# Temp_Measurements.net
KiCad netlist of a schematic drawn in Altium Designer
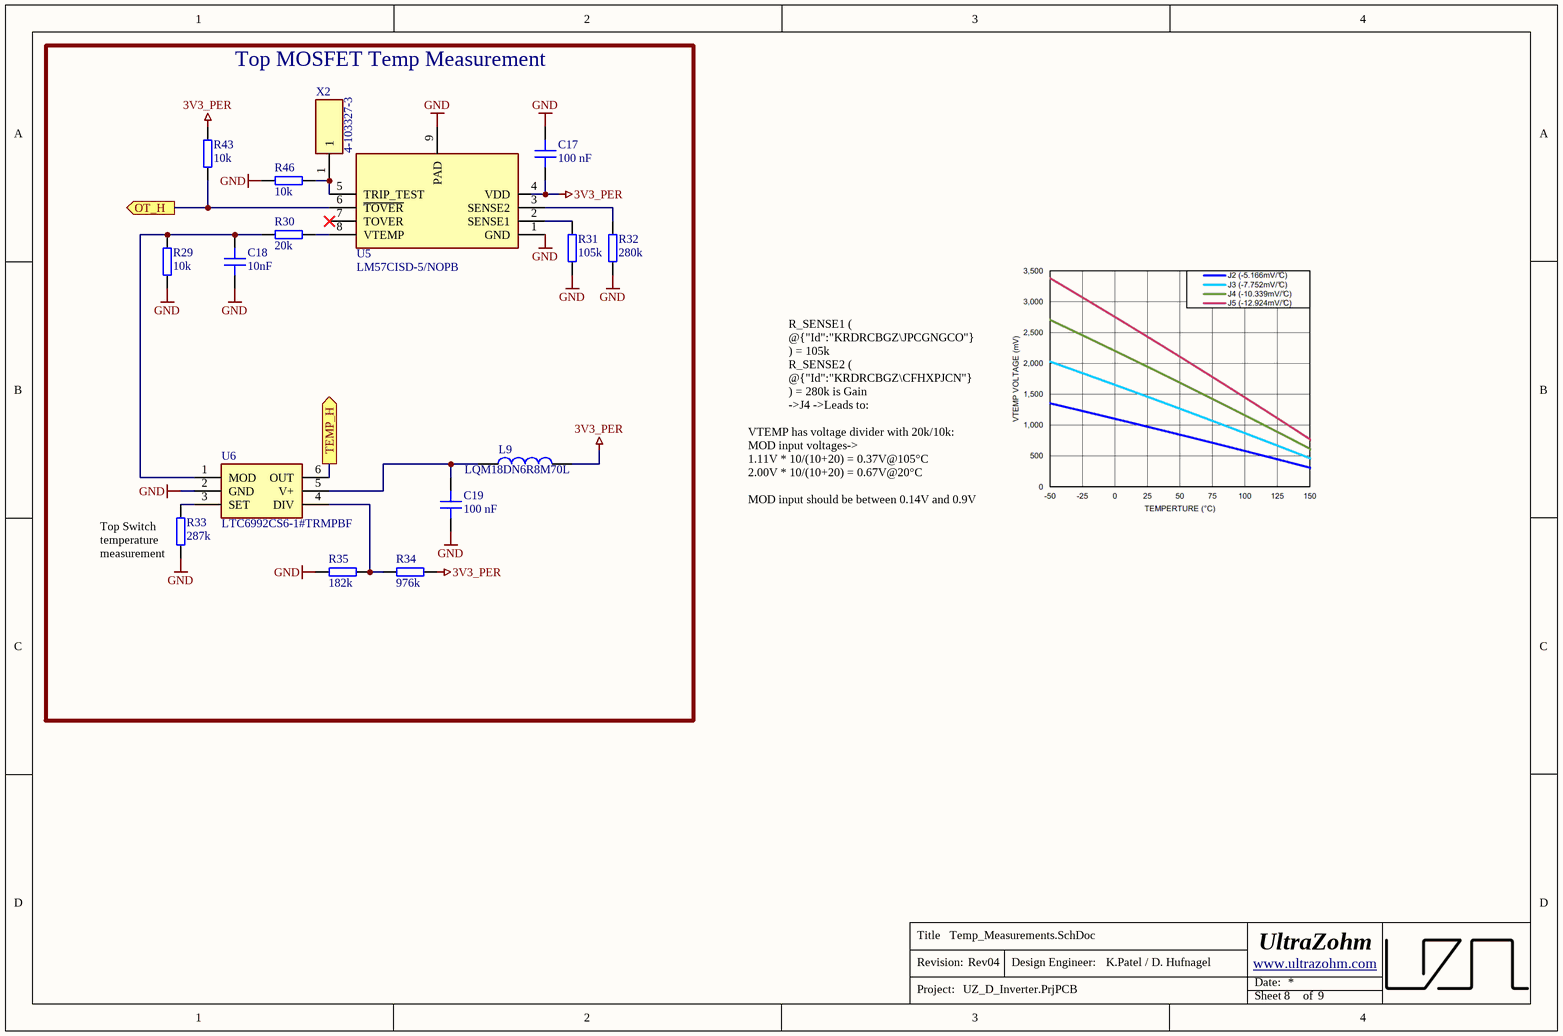
[diagram p0: Temp_Measurements.SchDoc]

(export (version "E")
  (design (tool "Eeschema 10.0.6"))
  (components
    (comp (ref "C17")
      (value "100 nF")
      (footprint "C_0603")
      (description "100V 100nF X7S ±10% 0603 Multilayer Ceramic Capacitors MLCC - SMD/SMT ROHS")
      (fields
        (field (name "MANUFACTURER PART NUMBER") "C1608X7S2A104KT000N")
        (field (name "MANUFACTURER") "TDK")
        (field (name "CREATED FROM") "AGeiger")
      )
      (libsource (lib "user") (part "Capacitor"))
    )
    (comp (ref "C18")
      (value "10nF")
      (footprint "C_0603")
      (description "50V 10nF 2X1 ±10%")
      (fields
        (field (name "MANUFACTURER PART NUMBER") "CT41G-0603-2X1-50V-0.01μF-K(N)")
        (field (name "MANUFACTURER") "TORCH")
        (field (name "CREATED FROM") "KIlhan")
      )
      (libsource (lib "user") (part "Capacitor"))
    )
    (comp (ref "C19")
      (value "100 nF")
      (footprint "C_0603")
      (description "100V 100nF X7S ±10% 0603 Multilayer Ceramic Capacitors MLCC - SMD/SMT ROHS")
      (fields
        (field (name "MANUFACTURER PART NUMBER") "C1608X7S2A104KT000N")
        (field (name "MANUFACTURER") "TDK")
        (field (name "CREATED FROM") "AGeiger")
      )
      (libsource (lib "user") (part "Capacitor"))
    )
    (comp (ref "L9")
      (value "LQM18DN6R8M70L")
      (footprint "INDC1608X95N")
      (description "6.8µH, 120mA, 0603, 740mOhm, 20%")
      (fields
        (field (name "MF") "EPCOS / TDK")
        (field (name "MPN") "B82464G4154M")
        (field (name "CREATED FROM") "DHufnagel")
      )
      (libsource (lib "user") (part "B82464G4154M"))
    )
    (comp (ref "R29")
      (value "10k")
      (footprint "RES 0603_1608")
      (description "SMD resistor E24 series")
      (fields
        (field (name "MANUFACTURER PART NUMBER") "RK73B1JTTD103J")
        (field (name "MANUFACTURER") "KOA Speer")
        (field (name "CREATED FROM") "MGremer")
      )
      (libsource (lib "user") (part "Resistor"))
    )
    (comp (ref "R30")
      (value "20k")
      (footprint "RES 0603_1608")
      (description "SMD resistor E24 series")
      (fields
        (field (name "MANUFACTURER PART NUMBER") "RK73B1JTTD203J")
        (field (name "MANUFACTURER") "KOA Speer")
        (field (name "CREATED FROM") "MGremer")
      )
      (libsource (lib "user") (part "Resistor"))
    )
    (comp (ref "R31")
      (value "105k")
      (footprint "RES 0603_1608")
      (description "SMD resistor 1%, 50V, 100ppm")
      (fields
        (field (name "MANUFACTURER PART NUMBER") "CR0603-FX-1053ELF")
        (field (name "MANUFACTURER") "Bourns")
        (field (name "CREATED FROM") "DHufnagel")
      )
      (libsource (lib "user") (part "Resistor"))
    )
    (comp (ref "R32")
      (value "280k")
      (footprint "RES 0603_1608")
      (description "SMD resistor 1%, 50V, 100ppm")
      (fields
        (field (name "MANUFACTURER PART NUMBER") "CR0603-FX-2803ELF")
        (field (name "MANUFACTURER") "Bourns")
        (field (name "CREATED FROM") "DHufnagel")
      )
      (libsource (lib "user") (part "Resistor"))
    )
    (comp (ref "R33")
      (value "287k")
      (footprint "RES 0805_2012")
      (description "SMD resistor 1%")
      (fields
        (field (name "MANUFACTURER PART NUMBER") "ERJ-6ENF2873V")
        (field (name "MANUFACTURER") "Panasonic")
        (field (name "CREATED FROM") "MGremer")
      )
      (libsource (lib "user") (part "Resistor"))
    )
    (comp (ref "R34")
      (value "976k")
      (footprint "RES 0603_1608")
      (description "SMD resistor 1%, 50V, 100ppm")
      (fields
        (field (name "MANUFACTURER PART NUMBER") "CR0603-FX-9763ELF")
        (field (name "MANUFACTURER") "Bourns")
        (field (name "CREATED FROM") "DHufnagel")
      )
      (libsource (lib "user") (part "Resistor"))
    )
    (comp (ref "R35")
      (value "182k")
      (footprint "RES 0603_1608")
      (description "SMD resistor 1%, 50V, 100ppm")
      (fields
        (field (name "MANUFACTURER PART NUMBER") "CR0603-FX-1823ELF")
        (field (name "MANUFACTURER") "Bourns")
        (field (name "CREATED FROM") "DHufnagel")
      )
      (libsource (lib "user") (part "Resistor"))
    )
    (comp (ref "R43")
      (value "10k")
      (footprint "RES 0603_1608")
      (description "SMD resistor E24 series")
      (fields
        (field (name "MANUFACTURER PART NUMBER") "RK73B1JTTD103J")
        (field (name "MANUFACTURER") "KOA Speer")
        (field (name "CREATED FROM") "MGremer")
      )
      (libsource (lib "user") (part "Resistor"))
    )
    (comp (ref "R46")
      (value "10k")
      (footprint "RES 0603_1608")
      (description "SMD resistor E24 series")
      (fields
        (field (name "MANUFACTURER PART NUMBER") "RK73B1JTTD103J")
        (field (name "MANUFACTURER") "KOA Speer")
        (field (name "CREATED FROM") "MGremer")
      )
      (libsource (lib "user") (part "Resistor"))
    )
    (comp (ref "U5")
      (value "LM57CISD-5/NOPB")
      (footprint "SON50P250X250X80-9N")
      (description "Board Mount Temperature Sensor, -50 - 150°C")
      (fields
        (field (name "MANUFACTURER") "Texas Instruments")
        (field (name "LCSC PART NUMBER") "C2864092")
        (field (name "CREATED FROM") "DHufnagel")
      )
      (libsource (lib "user") (part "LM57CISD-10_NOPB"))
    )
    (comp (ref "U6")
      (value "LTC6992CS6-1#TRMPBF")
      (footprint "SOT95P280X100-6N")
      (description "Switching Controllers PWM with 0% to 100% Pulse Width Control")
      (fields
        (field (name "MANUFACTURER") "Analog Devices")
        (field (name "LCSC PART NUMBER") "C581034")
        (field (name "CREATED FROM") "AGeiger")
      )
      (libsource (lib "user") (part "LTC6992HS6-4#WTRMPBF"))
    )
    (comp (ref "X2")
      (value "4-103327-3")
      (footprint "1_Pin_Header")
      (description "Pin Header, 2.54mm, 1 Pin")
      (fields (field (name "MANUFACTURER") "TE Connectivity") (field (name "CREATED FROM") "DHufnagel"))
      (libsource (lib "user") (part "4-103327-3"))
    )
  )
  (nets
    (net (code "1") (name "/OT_H") (class "Default")
      (node (ref "R43") (pin "2") (pinfunction "2_2") (pintype "passive"))
      (node (ref "U5") (pin "6") (pinfunction "~{TOVER}_6") (pintype "passive"))
    )
    (net (code "2") (name "/TEMP_H") (class "Default")
      (node (ref "U6") (pin "6") (pinfunction "OUT_6") (pintype "passive"))
    )
    (net (code "3") (name "3V3_PER") (class "Default")
      (node (ref "C17") (pin "1") (pinfunction "1_1") (pintype "passive"))
      (node (ref "L9") (pin "2") (pinfunction "2_2") (pintype "passive"))
      (node (ref "R34") (pin "2") (pinfunction "2_2") (pintype "passive"))
      (node (ref "R43") (pin "1") (pinfunction "1_1") (pintype "passive"))
      (node (ref "U5") (pin "4") (pinfunction "VDD_4") (pintype "passive"))
    )
    (net (code "4") (name "GND") (class "Default")
      (node (ref "C17") (pin "2") (pinfunction "2_2") (pintype "passive"))
      (node (ref "C18") (pin "1") (pinfunction "1_1") (pintype "passive"))
      (node (ref "C19") (pin "1") (pinfunction "1_1") (pintype "passive"))
      (node (ref "R29") (pin "2") (pinfunction "2_2") (pintype "passive"))
      (node (ref "R31") (pin "1") (pinfunction "1_1") (pintype "passive"))
      (node (ref "R32") (pin "1") (pinfunction "1_1") (pintype "passive"))
      (node (ref "R33") (pin "1") (pinfunction "1_1") (pintype "passive"))
      (node (ref "R35") (pin "1") (pinfunction "1_1") (pintype "passive"))
      (node (ref "R46") (pin "2") (pinfunction "2_2") (pintype "passive"))
      (node (ref "U5") (pin "1") (pinfunction "GND_1") (pintype "passive"))
      (node (ref "U5") (pin "9") (pinfunction "PAD_9") (pintype "passive"))
      (node (ref "U6") (pin "2") (pinfunction "GND_2") (pintype "passive"))
    )
    (net (code "5") (name "Net-(U5-SENSE1)") (class "Default")
      (node (ref "R31") (pin "2") (pinfunction "2_2") (pintype "passive"))
      (node (ref "U5") (pin "2") (pinfunction "SENSE1_2") (pintype "passive"))
    )
    (net (code "6") (name "Net-(U5-SENSE2)") (class "Default")
      (node (ref "R32") (pin "2") (pinfunction "2_2") (pintype "passive"))
      (node (ref "U5") (pin "3") (pinfunction "SENSE2_3") (pintype "passive"))
    )
    (net (code "7") (name "Net-(U5-TRIP_TEST)") (class "Default")
      (node (ref "R46") (pin "1") (pinfunction "1_1") (pintype "passive"))
      (node (ref "U5") (pin "5") (pinfunction "TRIP_TEST_5") (pintype "passive"))
      (node (ref "X2") (pin "1") (pinfunction "1_1") (pintype "passive"))
    )
    (net (code "8") (name "Net-(U5-VTEMP)") (class "Default")
      (node (ref "R30") (pin "2") (pinfunction "2_2") (pintype "passive"))
      (node (ref "U5") (pin "8") (pinfunction "VTEMP_8") (pintype "passive"))
    )
    (net (code "9") (name "Net-(U6-DIV)") (class "Default")
      (node (ref "R34") (pin "1") (pinfunction "1_1") (pintype "passive"))
      (node (ref "R35") (pin "2") (pinfunction "2_2") (pintype "passive"))
      (node (ref "U6") (pin "4") (pinfunction "DIV_4") (pintype "passive"))
    )
    (net (code "10") (name "Net-(U6-MOD)") (class "Default")
      (node (ref "C18") (pin "2") (pinfunction "2_2") (pintype "passive"))
      (node (ref "R29") (pin "1") (pinfunction "1_1") (pintype "passive"))
      (node (ref "R30") (pin "1") (pinfunction "1_1") (pintype "passive"))
      (node (ref "U6") (pin "1") (pinfunction "MOD_1") (pintype "passive"))
    )
    (net (code "11") (name "Net-(U6-SET)") (class "Default")
      (node (ref "R33") (pin "2") (pinfunction "2_2") (pintype "passive"))
      (node (ref "U6") (pin "3") (pinfunction "SET_3") (pintype "passive"))
    )
    (net (code "12") (name "Net-(U6-V+)") (class "Default")
      (node (ref "C19") (pin "2") (pinfunction "2_2") (pintype "passive"))
      (node (ref "L9") (pin "1") (pinfunction "1_1") (pintype "passive"))
      (node (ref "U6") (pin "5") (pinfunction "V+_5") (pintype "passive"))
    )
    (net (code "13") (name "unconnected-(U5-TOVER-Pad7)") (class "Default")
      (node (ref "U5") (pin "7") (pinfunction "TOVER_7") (pintype "passive+no_connect"))
    )
  )
)
